# amp.net
KiCad netlist of a schematic drawn in EAGLE
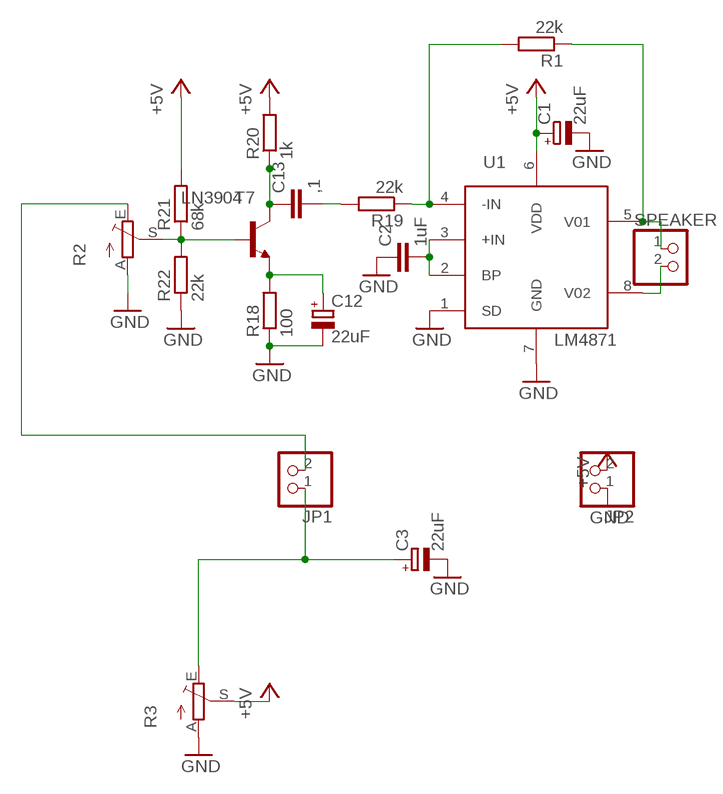
[diagram p0: schematic, sheet 1]

(export (version "E")
  (design (tool "Eeschema 10.0.6"))
  (components
    (comp (ref "C1")
      (value "22uF")
      (footprint "eagle-import:CT3528")
      (libsource (lib "eagle-import") (part "CPOL-EUCT3528"))
    )
    (comp (ref "C2")
      (value "1uF")
      (footprint "eagle-import:C0603")
      (libsource (lib "eagle-import") (part "C-EUC0603"))
    )
    (comp (ref "C3")
      (value "22uF")
      (footprint "eagle-import:CT3528")
      (libsource (lib "eagle-import") (part "CPOL-EUCT3528"))
    )
    (comp (ref "C12")
      (value "22uF")
      (footprint "eagle-import:CT3528")
      (libsource (lib "eagle-import") (part "CPOL-EUCT3528"))
    )
    (comp (ref "C13")
      (value ",1")
      (footprint "eagle-import:C0603")
      (libsource (lib "eagle-import") (part "C-EUC0603"))
    )
    (comp (ref "JP1")
      (value "PINHD-1X2")
      (footprint "eagle-import:1X02")
      (libsource (lib "eagle-import") (part "PINHD-1X2"))
    )
    (comp (ref "JP2")
      (value "PINHD-1X2")
      (footprint "eagle-import:1X02")
      (libsource (lib "eagle-import") (part "PINHD-1X2"))
    )
    (comp (ref "R1")
      (value "22k")
      (footprint "eagle-import:R0603")
      (libsource (lib "eagle-import") (part "R-EU_R0603"))
    )
    (comp (ref "R2")
      (value "TRIM_EU-LI15")
      (footprint "eagle-import:LI15")
      (libsource (lib "eagle-import") (part "TRIM_EU-LI15"))
    )
    (comp (ref "R3")
      (value "TRIM_EU-LI15")
      (footprint "eagle-import:LI15")
      (libsource (lib "eagle-import") (part "TRIM_EU-LI15"))
    )
    (comp (ref "R18")
      (value "100")
      (footprint "eagle-import:R0603")
      (libsource (lib "eagle-import") (part "R-EU_R0603"))
    )
    (comp (ref "R19")
      (value "22k")
      (footprint "eagle-import:R0603")
      (libsource (lib "eagle-import") (part "R-EU_R0603"))
    )
    (comp (ref "R20")
      (value "1k")
      (footprint "eagle-import:R0603")
      (libsource (lib "eagle-import") (part "R-EU_R0603"))
    )
    (comp (ref "R21")
      (value "68k")
      (footprint "eagle-import:R0603")
      (libsource (lib "eagle-import") (part "R-EU_R0603"))
    )
    (comp (ref "R22")
      (value "22k")
      (footprint "eagle-import:R0603")
      (libsource (lib "eagle-import") (part "R-EU_R0603"))
    )
    (comp (ref "SPEAKER")
      (value "PINHD-1X2")
      (footprint "eagle-import:1X02")
      (libsource (lib "eagle-import") (part "PINHD-1X2"))
    )
    (comp (ref "T7")
      (value "LN3904")
      (footprint "eagle-import:SOT23-BEC")
      (libsource (lib "eagle-import") (part "-NPN-SOT23-BECBC848"))
    )
    (comp (ref "U1")
      (value "LM4871")
      (footprint "eagle-import:ICS_SOP08")
      (libsource (lib "eagle-import") (part "ICS_LM4871"))
    )
  )
  (nets
    (net (code "1") (name "+5V") (class "Default")
      (node (ref "C1") (pin "+") (pinfunction "+_+") (pintype "passive"))
      (node (ref "JP2") (pin "2") (pinfunction "2_2") (pintype "passive"))
      (node (ref "R20") (pin "2") (pinfunction "2_2") (pintype "passive"))
      (node (ref "R21") (pin "2") (pinfunction "2_2") (pintype "passive"))
      (node (ref "R3") (pin "S") (pinfunction "S_S") (pintype "passive"))
      (node (ref "U1") (pin "6") (pinfunction "VDD_6") (pintype "power_in"))
    )
    (net (code "2") (name "GND") (class "Default")
      (node (ref "C1") (pin "-") (pinfunction "-_-") (pintype "passive"))
      (node (ref "C12") (pin "-") (pinfunction "-_-") (pintype "passive"))
      (node (ref "C2") (pin "1") (pinfunction "1_1") (pintype "passive"))
      (node (ref "C3") (pin "-") (pinfunction "-_-") (pintype "passive"))
      (node (ref "JP2") (pin "1") (pinfunction "1_1") (pintype "passive"))
      (node (ref "R18") (pin "1") (pinfunction "1_1") (pintype "passive"))
      (node (ref "R2") (pin "A") (pinfunction "A_A") (pintype "passive"))
      (node (ref "R22") (pin "1") (pinfunction "1_1") (pintype "passive"))
      (node (ref "R3") (pin "A") (pinfunction "A_A") (pintype "passive"))
      (node (ref "U1") (pin "1") (pinfunction "SD_1") (pintype "input"))
      (node (ref "U1") (pin "7") (pinfunction "GND_7") (pintype "power_in"))
    )
    (net (code "3") (name "Net-(C3-Pad+)") (class "Default")
      (node (ref "C3") (pin "+") (pinfunction "+_+") (pintype "passive"))
      (node (ref "JP1") (pin "1") (pinfunction "1_1") (pintype "passive"))
      (node (ref "R3") (pin "E") (pinfunction "E_E") (pintype "passive"))
    )
    (net (code "4") (name "Net-(C12-Pad+)") (class "Default")
      (node (ref "C12") (pin "+") (pinfunction "+_+") (pintype "passive"))
      (node (ref "R18") (pin "2") (pinfunction "2_2") (pintype "passive"))
      (node (ref "T7") (pin "E") (pinfunction "E_E") (pintype "passive"))
    )
    (net (code "5") (name "Net-(C13-Pad1)") (class "Default")
      (node (ref "C13") (pin "1") (pinfunction "1_1") (pintype "passive"))
      (node (ref "R20") (pin "1") (pinfunction "1_1") (pintype "passive"))
      (node (ref "T7") (pin "C") (pinfunction "C_C") (pintype "passive"))
    )
    (net (code "6") (name "Net-(C13-Pad2)") (class "Default")
      (node (ref "C13") (pin "2") (pinfunction "2_2") (pintype "passive"))
      (node (ref "R19") (pin "2") (pinfunction "2_2") (pintype "passive"))
    )
    (net (code "7") (name "Net-(JP1-Pad2)") (class "Default")
      (node (ref "JP1") (pin "2") (pinfunction "2_2") (pintype "passive"))
      (node (ref "R2") (pin "E") (pinfunction "E_E") (pintype "passive"))
    )
    (net (code "8") (name "Net-(R2-PadS)") (class "Default")
      (node (ref "R2") (pin "S") (pinfunction "S_S") (pintype "passive"))
      (node (ref "R21") (pin "1") (pinfunction "1_1") (pintype "passive"))
      (node (ref "R22") (pin "2") (pinfunction "2_2") (pintype "passive"))
      (node (ref "T7") (pin "B") (pinfunction "B_B") (pintype "passive"))
    )
    (net (code "9") (name "Net-(U1-+IN)") (class "Default")
      (node (ref "C2") (pin "2") (pinfunction "2_2") (pintype "passive"))
      (node (ref "U1") (pin "2") (pinfunction "BP_2") (pintype "output"))
      (node (ref "U1") (pin "3") (pinfunction "+IN_3") (pintype "input"))
    )
    (net (code "10") (name "Net-(U1--IN)") (class "Default")
      (node (ref "R1") (pin "2") (pinfunction "2_2") (pintype "passive"))
      (node (ref "R19") (pin "1") (pinfunction "1_1") (pintype "passive"))
      (node (ref "U1") (pin "4") (pinfunction "-IN_4") (pintype "input"))
    )
    (net (code "11") (name "Net-(U1-V01)") (class "Default")
      (node (ref "R1") (pin "1") (pinfunction "1_1") (pintype "passive"))
      (node (ref "SPEAKER") (pin "1") (pinfunction "1_1") (pintype "passive"))
      (node (ref "U1") (pin "5") (pinfunction "V01_5") (pintype "output"))
    )
    (net (code "12") (name "Net-(U1-V02)") (class "Default")
      (node (ref "SPEAKER") (pin "2") (pinfunction "2_2") (pintype "passive"))
      (node (ref "U1") (pin "8") (pinfunction "V02_8") (pintype "output"))
    )
  )
)
